# LorRaAdapter.net
KiCad netlist of a schematic drawn in EAGLE
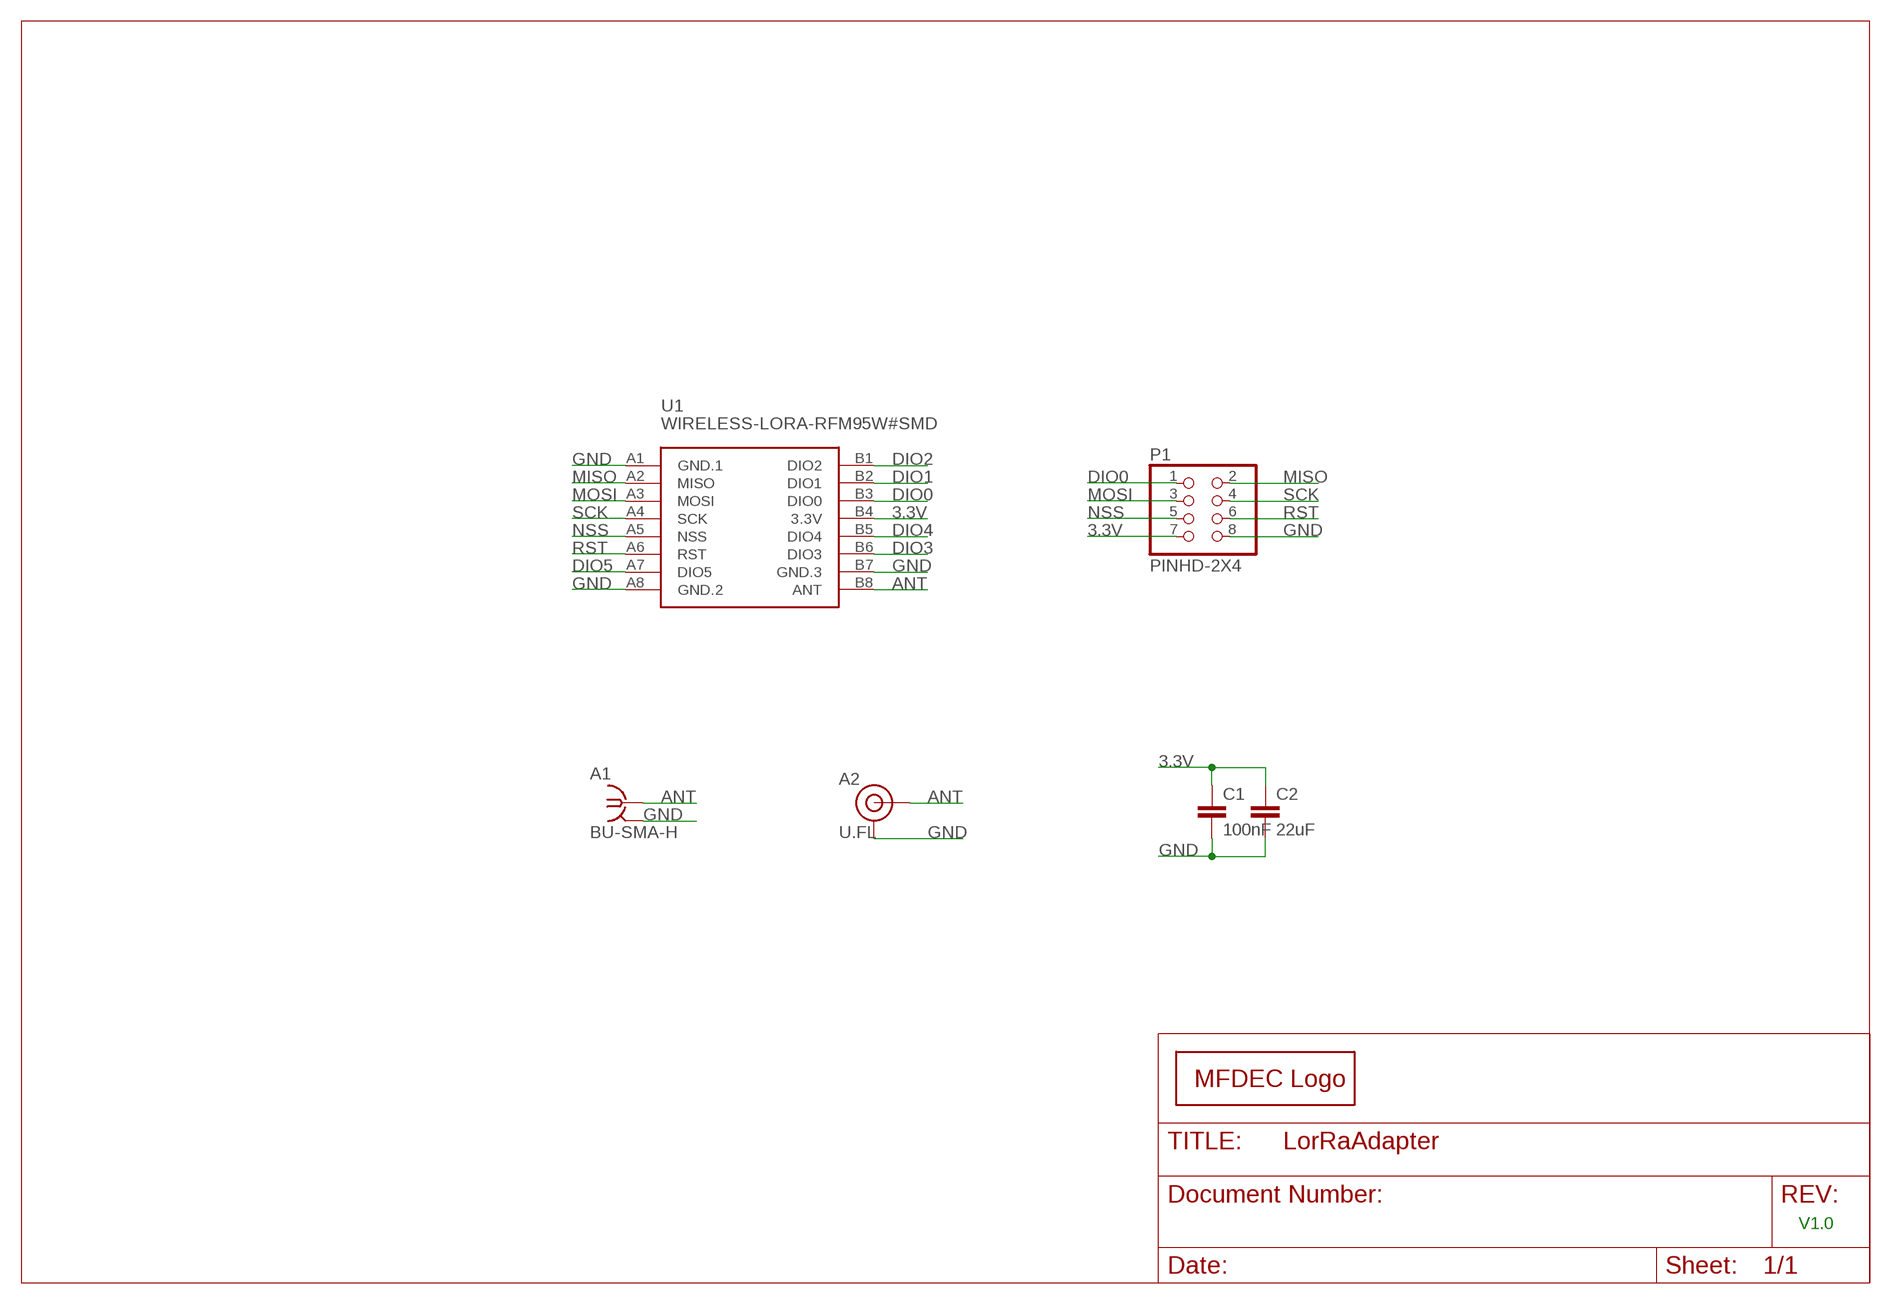
[diagram p0: schematic, sheet 1]

(export (version "E")
  (design (tool "Eeschema 10.0.6"))
  (components
    (comp (ref "A1")
      (value "BU-SMA-H")
      (footprint "eagle-import:BU-SMA-H")
      (libsource (lib "eagle-import") (part "BU-SMA-H"))
    )
    (comp (ref "A2")
      (value "U.FL")
      (footprint "eagle-import:U.FL")
      (libsource (lib "eagle-import") (part "U.FL2PIN"))
    )
    (comp (ref "C1")
      (value "100nF")
      (footprint "eagle-import:C0603")
      (libsource (lib "eagle-import") (part "C-EUC0603"))
    )
    (comp (ref "C2")
      (value "22uF")
      (footprint "eagle-import:C1206")
      (libsource (lib "eagle-import") (part "C-EUC1206"))
    )
    (comp (ref "LOGO1")
      (value "MFDECLOGO_SQ_5MM")
      (footprint "eagle-import:MFDEC_SQ_5MM")
      (libsource (lib "eagle-import") (part "MFDECLOGO_SQ_5MM"))
    )
    (comp (ref "P1")
      (value "PINHD-2X4")
      (footprint "eagle-import:2X04")
      (libsource (lib "eagle-import") (part "PINHD-2X4"))
    )
    (comp (ref "U1")
      (value "WIRELESS-LORA-RFM95W#SMD")
      (footprint "eagle-import:WIRELESS-LORA-RFM95W#SMD")
      (libsource (lib "eagle-import") (part "WIRELESS-LORA-RFM95W#SMD"))
    )
  )
  (nets
    (net (code "1") (name "/3.3V") (class "Default")
      (node (ref "C1") (pin "1") (pinfunction "1_1") (pintype "passive"))
      (node (ref "C2") (pin "1") (pinfunction "1_1") (pintype "passive"))
      (node (ref "P1") (pin "7") (pinfunction "7_7") (pintype "passive"))
      (node (ref "U1") (pin "B4") (pinfunction "3.3V_B4") (pintype "power_in"))
    )
    (net (code "2") (name "/ANT") (class "Default")
      (node (ref "A1") (pin "1") (pinfunction "1_1") (pintype "passive"))
      (node (ref "A2") (pin "FEED") (pinfunction "SIGNAL_FEED") (pintype "bidirectional"))
      (node (ref "U1") (pin "B8") (pinfunction "ANT_B8") (pintype "passive"))
    )
    (net (code "3") (name "/DIO0") (class "Default")
      (node (ref "P1") (pin "1") (pinfunction "1_1") (pintype "passive"))
      (node (ref "U1") (pin "B3") (pinfunction "DIO0_B3") (pintype "bidirectional"))
    )
    (net (code "4") (name "/DIO1") (class "Default")
      (node (ref "U1") (pin "B2") (pinfunction "DIO1_B2") (pintype "bidirectional"))
    )
    (net (code "5") (name "/DIO2") (class "Default")
      (node (ref "U1") (pin "B1") (pinfunction "DIO2_B1") (pintype "bidirectional"))
    )
    (net (code "6") (name "/DIO3") (class "Default")
      (node (ref "U1") (pin "B6") (pinfunction "DIO3_B6") (pintype "bidirectional"))
    )
    (net (code "7") (name "/DIO4") (class "Default")
      (node (ref "U1") (pin "B5") (pinfunction "DIO4_B5") (pintype "bidirectional"))
    )
    (net (code "8") (name "/DIO5") (class "Default")
      (node (ref "U1") (pin "A7") (pinfunction "DIO5_A7") (pintype "bidirectional"))
    )
    (net (code "9") (name "/GND") (class "Default")
      (node (ref "A1") (pin "2") (pinfunction "2_2") (pintype "passive"))
      (node (ref "A1") (pin "3") (pinfunction "2_3") (pintype "passive"))
      (node (ref "A1") (pin "4") (pinfunction "2_4") (pintype "passive"))
      (node (ref "A1") (pin "5") (pinfunction "2_5") (pintype "passive"))
      (node (ref "A2") (pin "1") (pinfunction "GND_1") (pintype "bidirectional"))
      (node (ref "A2") (pin "2") (pinfunction "GND_2") (pintype "bidirectional"))
      (node (ref "C1") (pin "2") (pinfunction "2_2") (pintype "passive"))
      (node (ref "C2") (pin "2") (pinfunction "2_2") (pintype "passive"))
      (node (ref "P1") (pin "8") (pinfunction "8_8") (pintype "passive"))
      (node (ref "U1") (pin "A1") (pinfunction "GND.1_A1") (pintype "power_in"))
      (node (ref "U1") (pin "A8") (pinfunction "GND.2_A8") (pintype "power_in"))
      (node (ref "U1") (pin "B7") (pinfunction "GND.3_B7") (pintype "power_in"))
    )
    (net (code "10") (name "/MISO") (class "Default")
      (node (ref "P1") (pin "2") (pinfunction "2_2") (pintype "passive"))
      (node (ref "U1") (pin "A2") (pinfunction "MISO_A2") (pintype "bidirectional"))
    )
    (net (code "11") (name "/MOSI") (class "Default")
      (node (ref "P1") (pin "3") (pinfunction "3_3") (pintype "passive"))
      (node (ref "U1") (pin "A3") (pinfunction "MOSI_A3") (pintype "bidirectional"))
    )
    (net (code "12") (name "/NSS") (class "Default")
      (node (ref "P1") (pin "5") (pinfunction "5_5") (pintype "passive"))
      (node (ref "U1") (pin "A5") (pinfunction "NSS_A5") (pintype "bidirectional"))
    )
    (net (code "13") (name "/RST") (class "Default")
      (node (ref "P1") (pin "6") (pinfunction "6_6") (pintype "passive"))
      (node (ref "U1") (pin "A6") (pinfunction "RST_A6") (pintype "bidirectional"))
    )
    (net (code "14") (name "/SCK") (class "Default")
      (node (ref "P1") (pin "4") (pinfunction "4_4") (pintype "passive"))
      (node (ref "U1") (pin "A4") (pinfunction "SCK_A4") (pintype "bidirectional"))
    )
  )
)
